# Faulhaber_Temp_sensor_w_CPU.net
KiCad netlist of a schematic drawn in EAGLE
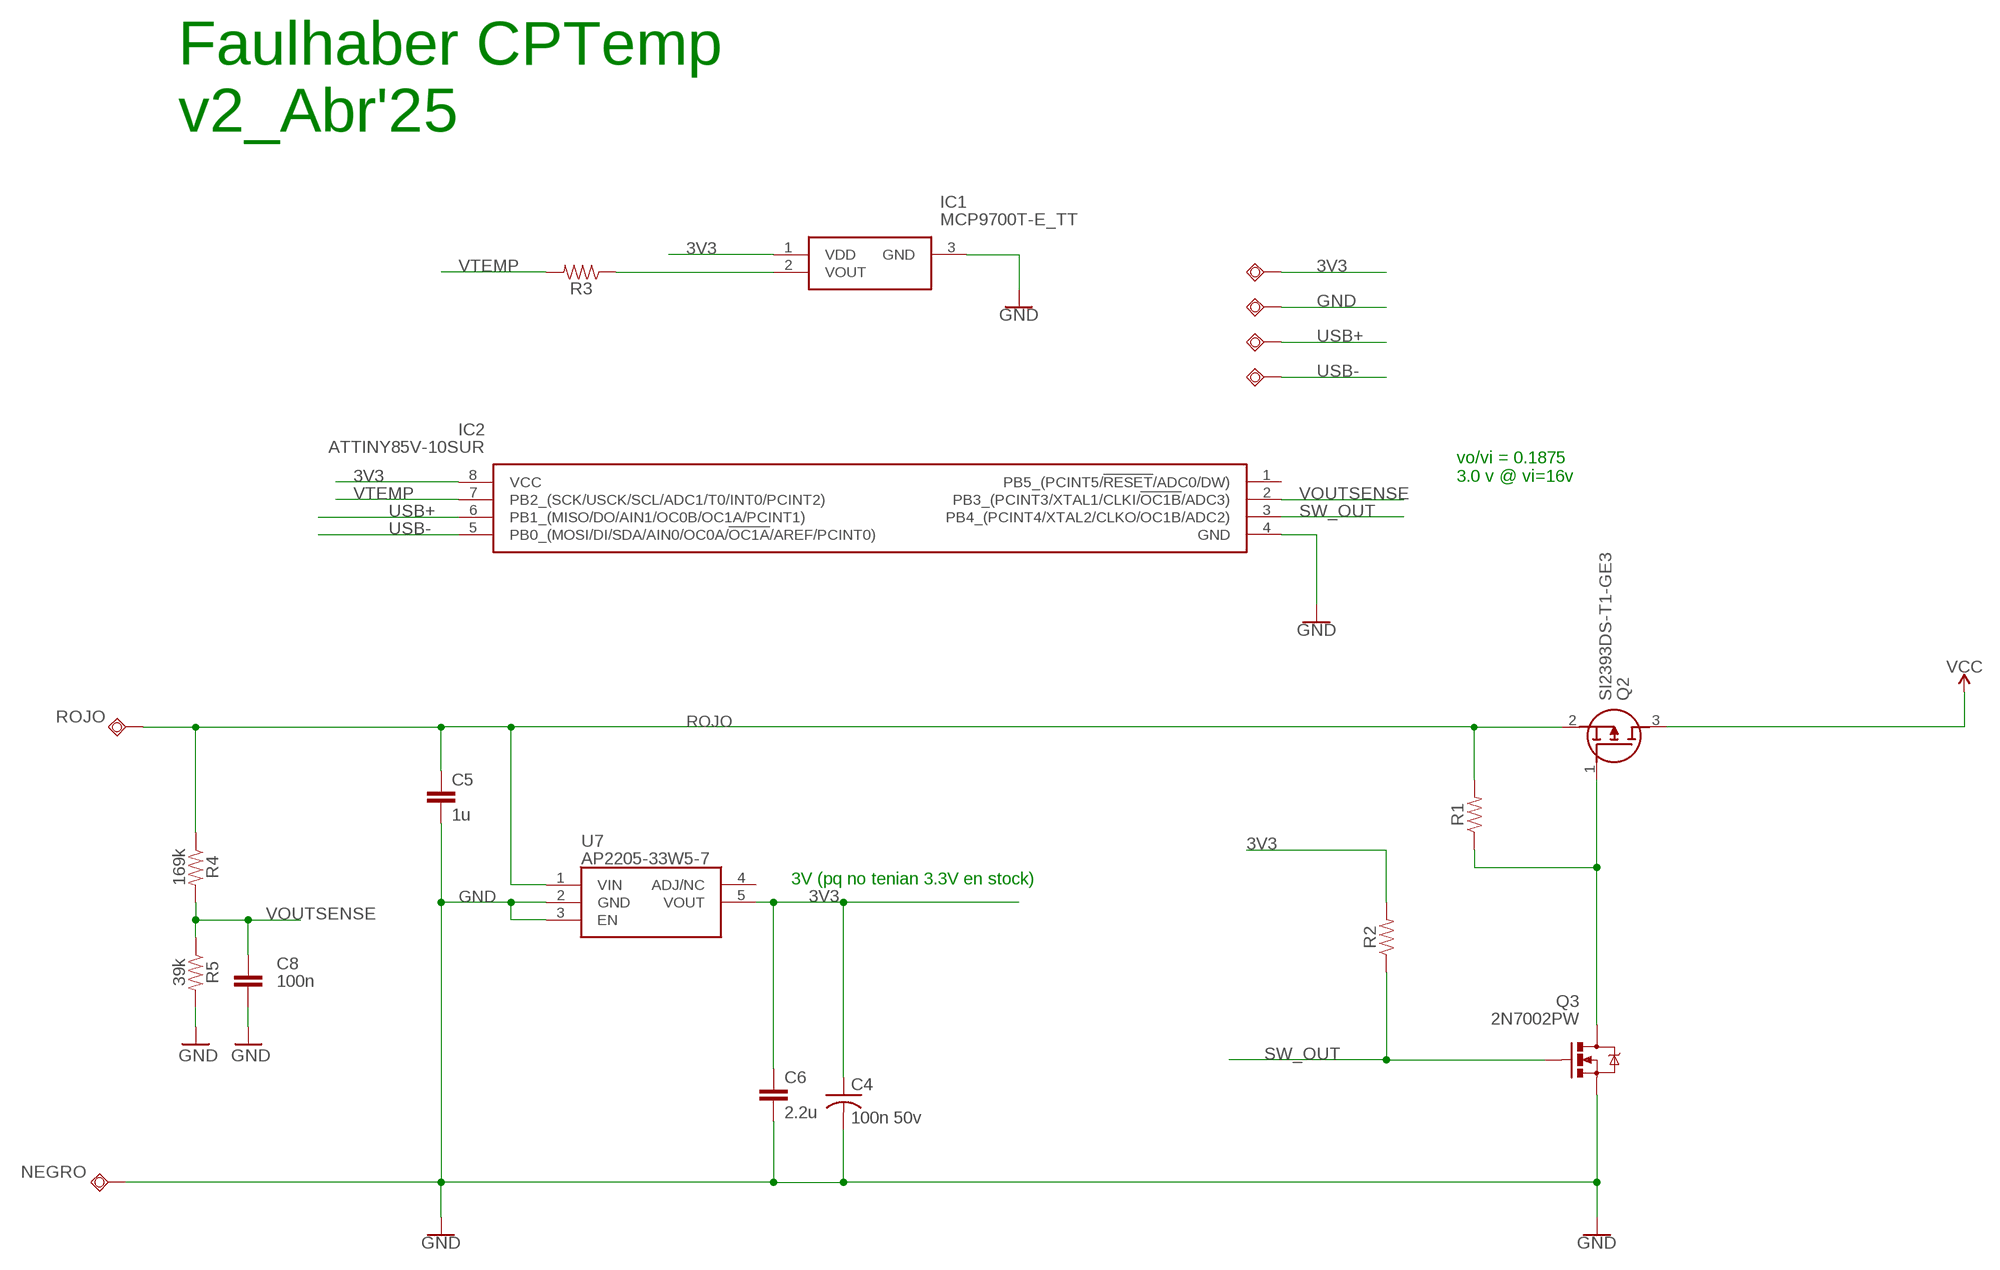
[diagram p0: schematic, sheet 1]

(export (version "E")
  (design (tool "Eeschema 10.0.6"))
  (components
    (comp (ref "3V3")
      (value "TESTPAD_TPSQB1,27")
      (footprint "eagle-import:TESTPAD_B1,27")
      (libsource (lib "eagle-import") (part "TESTPAD_TPSQB1,27"))
    )
    (comp (ref "C4")
      (value "100n 50v")
      (footprint "eagle-import:C0805")
      (libsource (lib "eagle-import") (part "C-USC0805"))
    )
    (comp (ref "C5")
      (value "1u")
      (footprint "eagle-import:0603-CAP")
      (libsource (lib "eagle-import") (part "4.7UF-6.3V-10%(0603)0603"))
    )
    (comp (ref "C6")
      (value "2.2u")
      (footprint "eagle-import:0603-CAP")
      (libsource (lib "eagle-import") (part "4.7UF-6.3V-10%(0603)0603"))
    )
    (comp (ref "C8")
      (value "100n")
      (footprint "eagle-import:0603")
      (libsource (lib "eagle-import") (part "0.1UF-0603-25V-(+80/-20%)"))
    )
    (comp (ref "GND")
      (value "TESTPAD_TPSQB1,27")
      (footprint "eagle-import:TESTPAD_B1,27")
      (libsource (lib "eagle-import") (part "TESTPAD_TPSQB1,27"))
    )
    (comp (ref "IC1")
      (value "MCP9700T-E_TT")
      (footprint "eagle-import:SOT95P237X112-3N")
      (fields
        (field (name "ARROW_PART_NUMBER") "MCP9700T-E/TT")
        (field (name "MOUSER_PART_NUMBER") "579-MCP9700T-E/TT")
      )
      (libsource (lib "eagle-import") (part "MCP9700T-E_TT"))
    )
    (comp (ref "IC2")
      (value "ATTINY85V-10SUR")
      (footprint "eagle-import:SOIC127P798X216-8N")
      (fields (field (name "FARNELL2_PART_NUMBER") "2851618RL"))
      (libsource (lib "eagle-import") (part "ATTINY85V-10SUR"))
    )
    (comp (ref "NEGRO")
      (value "TESTPAD_TPSQTP10SQ")
      (footprint "eagle-import:TESTPAD_TP10SQ")
      (libsource (lib "eagle-import") (part "BeagleBone_Blue_R3_5828899_TESTPAD_TPSQTP10SQ"))
    )
    (comp (ref "Q2")
      (value "SI2393DS-T1-GE3")
      (footprint "eagle-import:SOT95P237X112-3N")
      (fields (field (name "MOUSER_PART_NUMBER") "78-SI2393DS-T1-GE3"))
      (libsource (lib "eagle-import") (part "SI2393DS-T1-GE3"))
    )
    (comp (ref "Q3")
      (value "2N7002PW")
      (footprint "eagle-import:SOT323")
      (libsource (lib "eagle-import") (part "MOSFET-NCHANNEL2N7002PW"))
    )
    (comp (ref "R1")
      (value "RESISTOR0603")
      (footprint "eagle-import:0603")
      (libsource (lib "eagle-import") (part "RESISTOR0603"))
    )
    (comp (ref "R2")
      (value "RESISTOR0603")
      (footprint "eagle-import:0603")
      (libsource (lib "eagle-import") (part "RESISTOR0603"))
    )
    (comp (ref "R3")
      (value "RESISTOR0603")
      (footprint "eagle-import:0603")
      (libsource (lib "eagle-import") (part "RESISTOR0603"))
    )
    (comp (ref "R4")
      (value "169k")
      (footprint "eagle-import:0603")
      (libsource (lib "eagle-import") (part "RESISTOR0603"))
    )
    (comp (ref "R5")
      (value "39k")
      (footprint "eagle-import:0603")
      (libsource (lib "eagle-import") (part "RESISTOR0603"))
    )
    (comp (ref "ROJO")
      (value "TESTPAD_TPSQTP10SQ")
      (footprint "eagle-import:TESTPAD_TP10SQ")
      (libsource (lib "eagle-import") (part "BeagleBone_Blue_R3_5828899_TESTPAD_TPSQTP10SQ"))
    )
    (comp (ref "U7")
      (value "AP2205-33W5-7")
      (footprint "eagle-import:SOT95P282X145-5N")
      (fields
        (field (name "MANUFACTURER_PART_NUMBER") "AP2205-W5-7")
        (field (name "MOUSER_PART_NUMBER") "621-AP2205-W5-7")
      )
      (libsource (lib "eagle-import") (part "AP2205-W5-7"))
    )
    (comp (ref "USB+")
      (value "TESTPAD_TPSQB1,27")
      (footprint "eagle-import:TESTPAD_B1,27")
      (libsource (lib "eagle-import") (part "TESTPAD_TPSQB1,27"))
    )
    (comp (ref "USB-")
      (value "TESTPAD_TPSQB1,27")
      (footprint "eagle-import:TESTPAD_B1,27")
      (libsource (lib "eagle-import") (part "TESTPAD_TPSQB1,27"))
    )
  )
  (nets
    (net (code "1") (name "/3V3") (class "Default")
      (node (ref "3V3") (pin "TP") (pinfunction "TP_TP") (pintype "input"))
      (node (ref "C4") (pin "1") (pinfunction "1_1") (pintype "passive"))
      (node (ref "C6") (pin "1") (pinfunction "1_1") (pintype "passive"))
      (node (ref "IC1") (pin "1") (pinfunction "VDD_1") (pintype "bidirectional"))
      (node (ref "IC2") (pin "8") (pinfunction "VCC_8") (pintype "bidirectional"))
      (node (ref "R2") (pin "2") (pinfunction "2_2") (pintype "passive"))
      (node (ref "U7") (pin "5") (pinfunction "VOUT_5") (pintype "bidirectional"))
    )
    (net (code "2") (name "/ROJO") (class "Default")
      (node (ref "C5") (pin "1") (pinfunction "1_1") (pintype "passive"))
      (node (ref "Q2") (pin "2") (pinfunction "S_2") (pintype "bidirectional"))
      (node (ref "R1") (pin "2") (pinfunction "2_2") (pintype "passive"))
      (node (ref "R4") (pin "1") (pinfunction "1_1") (pintype "passive"))
      (node (ref "ROJO") (pin "TP") (pinfunction "TP_TP") (pintype "input"))
      (node (ref "U7") (pin "1") (pinfunction "VIN_1") (pintype "bidirectional"))
    )
    (net (code "3") (name "/SW_OUT") (class "Default")
      (node (ref "IC2") (pin "3") (pinfunction "PB4_(PCINT4/XTAL2/CLKO/OC1B/ADC2)_3") (pintype "bidirectional"))
      (node (ref "Q3") (pin "1") (pinfunction "G_1") (pintype "passive"))
      (node (ref "R2") (pin "1") (pinfunction "1_1") (pintype "passive"))
    )
    (net (code "4") (name "/USB+") (class "Default")
      (node (ref "IC2") (pin "6") (pinfunction "PB1_(MISO/DO/AIN1/OC0B/OC1A/PCINT1)_6") (pintype "bidirectional"))
      (node (ref "USB+") (pin "TP") (pinfunction "TP_TP") (pintype "input"))
    )
    (net (code "5") (name "/USB-") (class "Default")
      (node (ref "IC2") (pin "5") (pinfunction "PB0_(MOSI/DI/SDA/AIN0/OC0A/~{OC1A}/AREF/PCINT0)_5") (pintype "bidirectional"))
      (node (ref "USB-") (pin "TP") (pinfunction "TP_TP") (pintype "input"))
    )
    (net (code "6") (name "/VOUTSENSE") (class "Default")
      (node (ref "C8") (pin "1") (pinfunction "1_1") (pintype "passive"))
      (node (ref "IC2") (pin "2") (pinfunction "PB3_(PCINT3/XTAL1/CLKI/~{OC1B}/ADC3)_2") (pintype "bidirectional"))
      (node (ref "R4") (pin "2") (pinfunction "2_2") (pintype "passive"))
      (node (ref "R5") (pin "1") (pinfunction "1_1") (pintype "passive"))
    )
    (net (code "7") (name "/VTEMP") (class "Default")
      (node (ref "IC2") (pin "7") (pinfunction "PB2_(SCK/USCK/SCL/ADC1/T0/INT0/PCINT2)_7") (pintype "bidirectional"))
      (node (ref "R3") (pin "2") (pinfunction "2_2") (pintype "passive"))
    )
    (net (code "8") (name "GND") (class "Default")
      (node (ref "C4") (pin "2") (pinfunction "2_2") (pintype "passive"))
      (node (ref "C5") (pin "2") (pinfunction "2_2") (pintype "passive"))
      (node (ref "C6") (pin "2") (pinfunction "2_2") (pintype "passive"))
      (node (ref "C8") (pin "2") (pinfunction "2_2") (pintype "passive"))
      (node (ref "GND") (pin "TP") (pinfunction "TP_TP") (pintype "input"))
      (node (ref "IC1") (pin "3") (pinfunction "GND_3") (pintype "bidirectional"))
      (node (ref "IC2") (pin "4") (pinfunction "GND_4") (pintype "bidirectional"))
      (node (ref "NEGRO") (pin "TP") (pinfunction "TP_TP") (pintype "input"))
      (node (ref "Q3") (pin "2") (pinfunction "S_2") (pintype "passive"))
      (node (ref "R5") (pin "2") (pinfunction "2_2") (pintype "passive"))
      (node (ref "U7") (pin "2") (pinfunction "GND_2") (pintype "bidirectional"))
      (node (ref "U7") (pin "3") (pinfunction "EN_3") (pintype "bidirectional"))
    )
    (net (code "9") (name "Net-(IC1-VOUT)") (class "Default")
      (node (ref "IC1") (pin "2") (pinfunction "VOUT_2") (pintype "bidirectional"))
      (node (ref "R3") (pin "1") (pinfunction "1_1") (pintype "passive"))
    )
    (net (code "10") (name "Net-(Q2-G)") (class "Default")
      (node (ref "Q2") (pin "1") (pinfunction "G_1") (pintype "bidirectional"))
      (node (ref "Q3") (pin "3") (pinfunction "D_3") (pintype "passive"))
      (node (ref "R1") (pin "1") (pinfunction "1_1") (pintype "passive"))
    )
    (net (code "11") (name "VCC") (class "Default")
      (node (ref "Q2") (pin "3") (pinfunction "D_3") (pintype "bidirectional"))
    )
    (net (code "12") (name "unconnected-(IC2-PB5_(PCINT5{slash}~{RESET}{slash}ADC0{slash}DW)-Pad1)") (class "Default")
      (node (ref "IC2") (pin "1") (pinfunction "PB5_(PCINT5/~{RESET}/ADC0/DW)_1") (pintype "bidirectional"))
    )
    (net (code "13") (name "unconnected-(U7-ADJ{slash}NC-Pad4)") (class "Default")
      (node (ref "U7") (pin "4") (pinfunction "ADJ/NC_4") (pintype "bidirectional"))
    )
  )
)
